# Data_Interlock.net
KiCad netlist of a schematic drawn in EAGLE
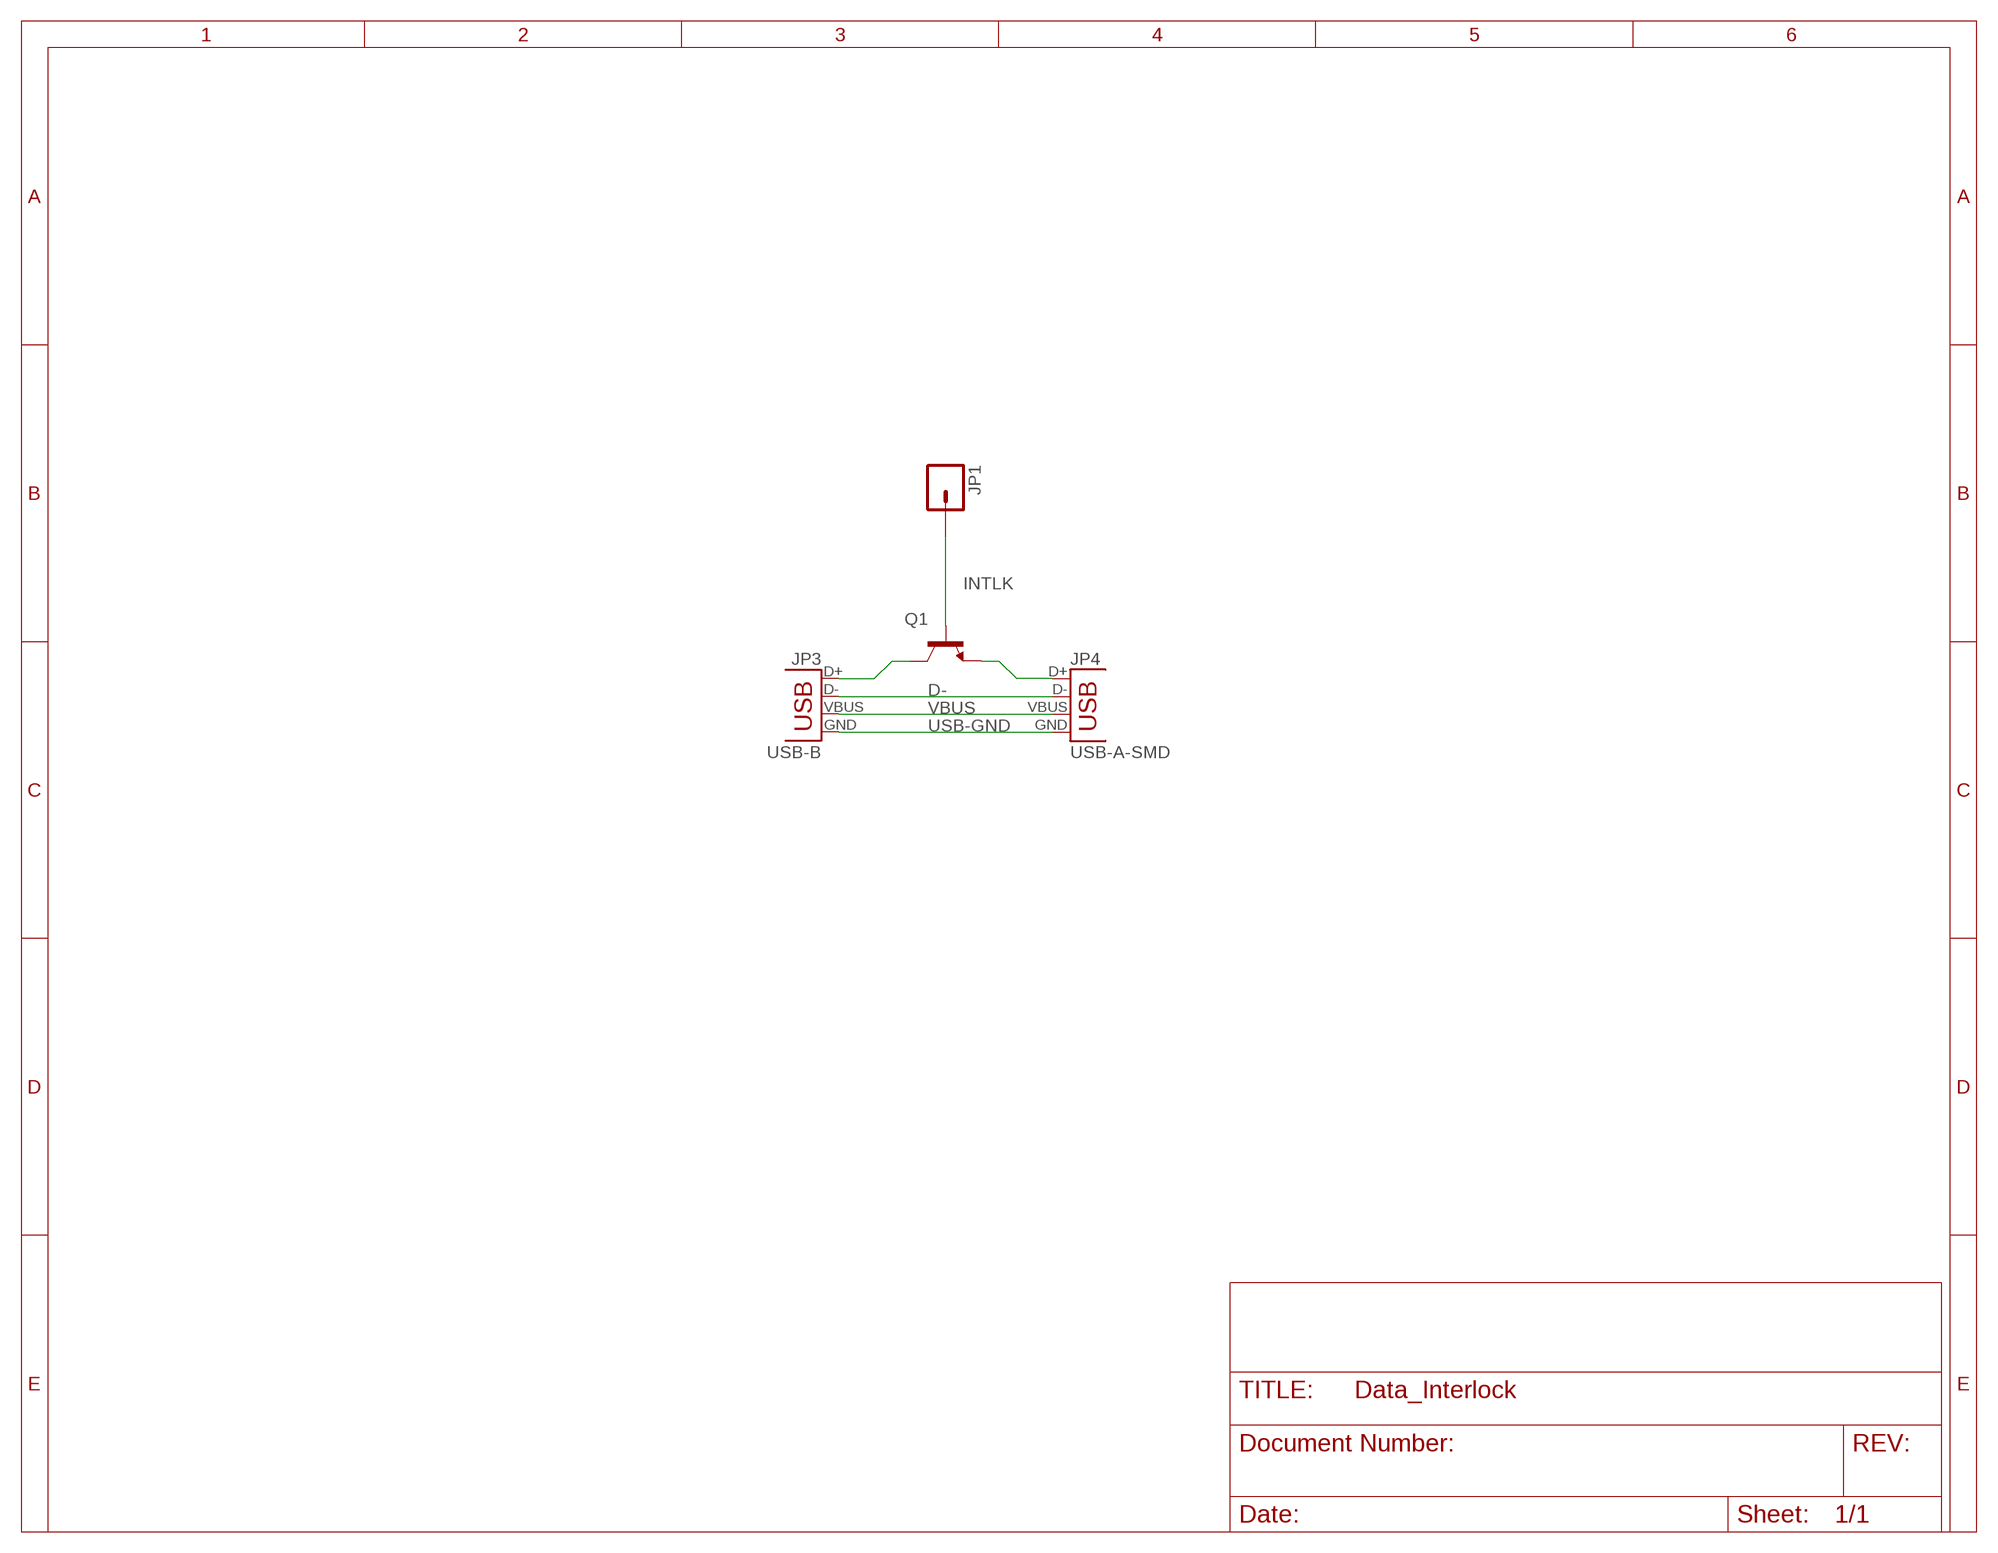
[diagram p0: schematic, sheet 1]

(export (version "E")
  (design (tool "Eeschema 10.0.6"))
  (components
    (comp (ref "JP1")
      (value "M01PTH_LONGPAD")
      (footprint "eagle-import:1X01_LONGPAD")
      (libsource (lib "eagle-import") (part "M01PTH_LONGPAD"))
    )
    (comp (ref "JP3")
      (value "USB-B")
      (footprint "eagle-import:USB-B-PTH")
      (libsource (lib "eagle-import") (part "USBPTH"))
    )
    (comp (ref "JP4")
      (value "USB-A-SMD")
      (footprint "eagle-import:USB-A-S-NOSILK-FEMALE")
      (libsource (lib "eagle-import") (part "USB-A-SMD"))
    )
    (comp (ref "Q1")
      (value "TRANSISTOR_NPNBC547")
      (footprint "eagle-import:TO-92-AMMO")
      (libsource (lib "eagle-import") (part "TRANSISTOR_NPNBC547"))
    )
  )
  (nets
    (net (code "1") (name "/D-") (class "Default")
      (node (ref "JP3") (pin "D-") (pinfunction "D-_D-") (pintype "bidirectional"))
      (node (ref "JP4") (pin "D-") (pinfunction "D-_D-") (pintype "bidirectional"))
    )
    (net (code "2") (name "/INTLK") (class "Default")
      (node (ref "JP1") (pin "1") (pinfunction "1_1") (pintype "passive"))
      (node (ref "Q1") (pin "2") (pinfunction "B_2") (pintype "passive"))
    )
    (net (code "3") (name "/USB-GND") (class "Default")
      (node (ref "JP3") (pin "GND") (pinfunction "GND_GND") (pintype "bidirectional"))
      (node (ref "JP4") (pin "GND") (pinfunction "GND_GND") (pintype "bidirectional"))
    )
    (net (code "4") (name "/VBUS") (class "Default")
      (node (ref "JP3") (pin "VBUS") (pinfunction "VBUS_VBUS") (pintype "bidirectional"))
      (node (ref "JP4") (pin "VBUS") (pinfunction "VBUS_VBUS") (pintype "bidirectional"))
    )
    (net (code "5") (name "Net-(Q1-C)") (class "Default")
      (node (ref "JP3") (pin "D+") (pinfunction "D+_D+") (pintype "bidirectional"))
      (node (ref "Q1") (pin "1") (pinfunction "C_1") (pintype "passive"))
    )
    (net (code "6") (name "Net-(Q1-E)") (class "Default")
      (node (ref "JP4") (pin "D+") (pinfunction "D+_D+") (pintype "bidirectional"))
      (node (ref "Q1") (pin "3") (pinfunction "E_3") (pintype "passive"))
    )
  )
)
